# Voeding.net
KiCad netlist of a schematic drawn in Altium Designer
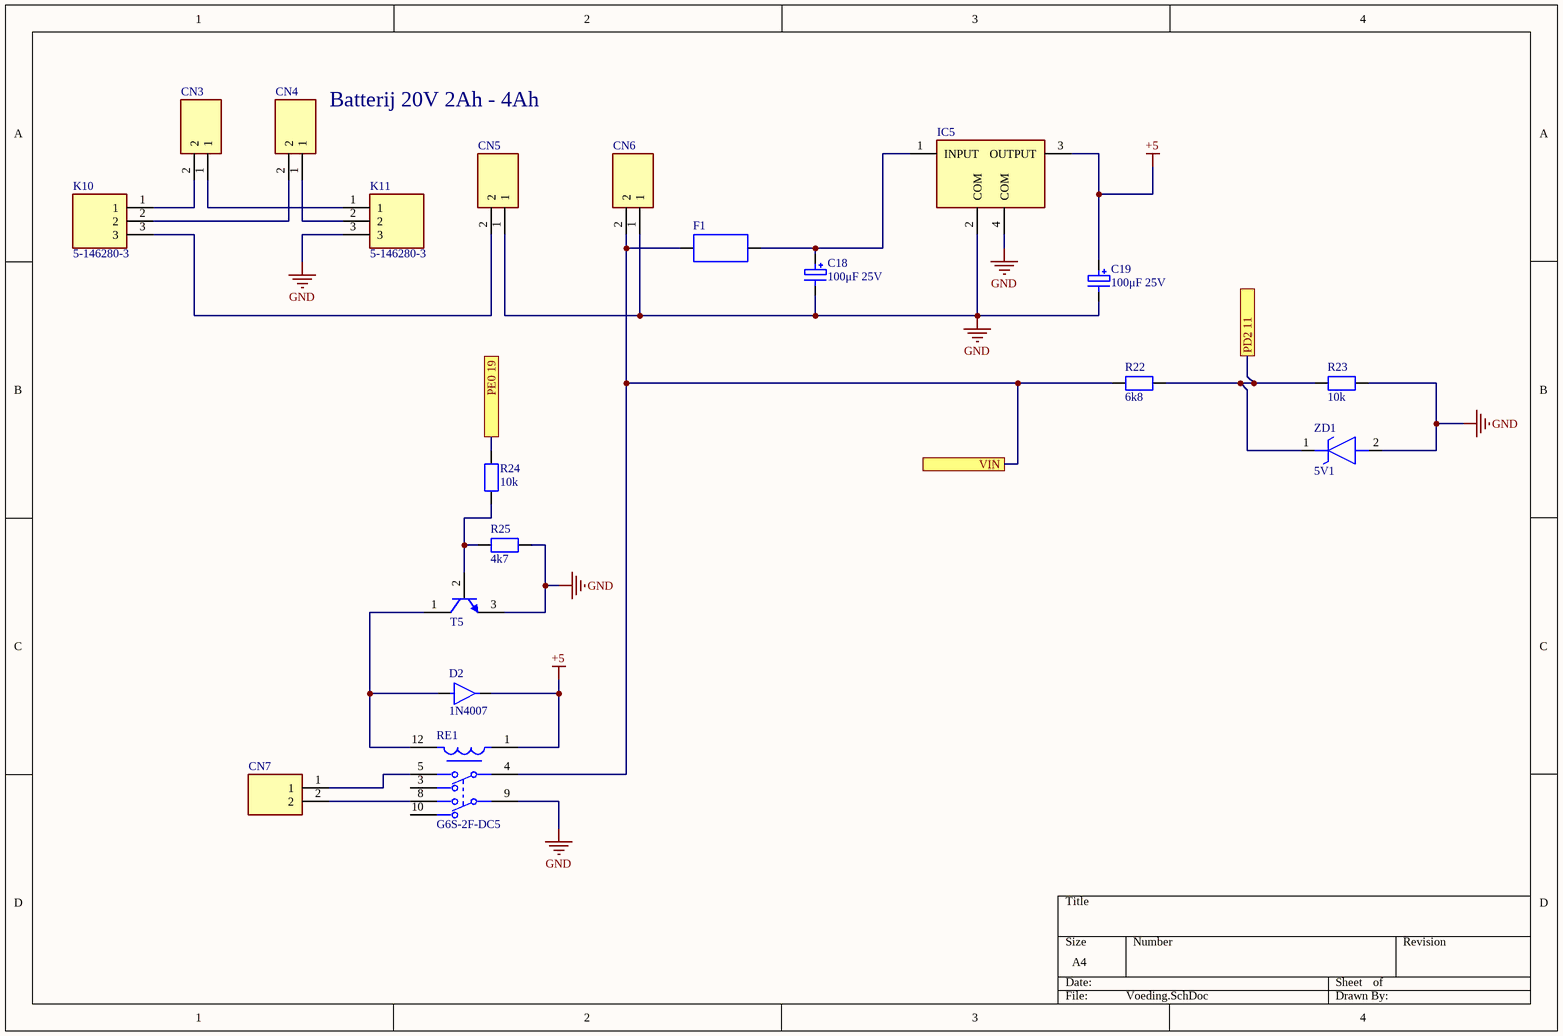
[diagram p0: Voeding.SchDoc]

(export (version "E")
  (design (tool "Eeschema 10.0.6"))
  (components
    (comp (ref "C18")
      (value "100μF 25V")
      (footprint "Elco 100uF 25V")
      (fields
        (field (name "PART NUMBER") "02015A270JAT2A")
        (field (name "MANUFACTURER") "AVX Interconnect / Elco")
      )
      (libsource (lib "Soldeerstation") (part "Condensator Elco"))
    )
    (comp (ref "C19")
      (value "100μF 25V")
      (footprint "Elco 100uF 25V")
      (fields
        (field (name "PART NUMBER") "02015A270JAT2A")
        (field (name "MANUFACTURER") "AVX Interconnect / Elco")
      )
      (libsource (lib "Soldeerstation") (part "Condensator Elco"))
    )
    (comp (ref "CN3")
      (value "282836-2")
      (footprint "Schroefconnector 2 Pin")
      (description "Connector")
      (libsource (lib "Soldeerstation") (part "Schroefconnector 2 Pin L"))
    )
    (comp (ref "CN4")
      (value "282836-2")
      (footprint "Schroefconnector 2 Pin")
      (description "Connector")
      (libsource (lib "Soldeerstation") (part "Schroefconnector 2 Pin L"))
    )
    (comp (ref "CN5")
      (value "282836-2")
      (footprint "Schroefconnector 2 Pin")
      (description "Connector")
      (libsource (lib "Soldeerstation") (part "Schroefconnector 2 Pin L"))
    )
    (comp (ref "CN6")
      (value "282836-2")
      (footprint "Schroefconnector 2 Pin")
      (description "Connector")
      (libsource (lib "Soldeerstation") (part "Schroefconnector 2 Pin L"))
    )
    (comp (ref "CN7")
      (value "282836-2")
      (footprint "Schroefconnector 2 Pin")
      (description "Connector")
      (libsource (lib "") (part "Schroefconnector 2 Pin L_1"))
    )
    (comp (ref "D2")
      (value "1N4007")
      (footprint "1N4007")
      (description "1000 V, 1 A")
      (fields (field (name "VOLTAGE") "100V"))
      (libsource (lib "Soldeerstation") (part "1N4007"))
    )
    (comp (ref "F1")
      (value "696101000002")
      (footprint "FuseHolder")
      (libsource (lib "Soldeerstation") (part "FuseHolder"))
    )
    (comp (ref "IC5")
      (value "TL780-05CKTTR")
      (footprint "DC-DC Convertor")
      (description "IC REG LIN 5V 1.5A DDPAK/TO263-3")
      (libsource (lib "Soldeerstation") (part "DC/DC Convertor"))
    )
    (comp (ref "K10")
      (value "5-146280-3")
      (footprint "3 Pin Header")
      (description "Connector 5-146280-3")
      (fields (field (name "MOUSER2 PART NUMBER") "571-5-146280-3"))
      (libsource (lib "") (part "3 Pin Header_1"))
    )
    (comp (ref "K11")
      (value "5-146280-3")
      (footprint "3 Pin Header")
      (description "Connector 5-146280-3")
      (fields (field (name "MOUSER2 PART NUMBER") "571-5-146280-3"))
      (libsource (lib "Soldeerstation") (part "3 Pin Header"))
    )
    (comp (ref "R22")
      (value "6k8")
      (footprint "Resistor")
      (description "Resistor")
      (fields (field (name "MANUFACTURER") "Vishay Dale") (field (name "PART NUMBER") "CRCW08050000Z0EA"))
      (libsource (lib "Soldeerstation") (part "Resistor"))
    )
    (comp (ref "R23")
      (value "10k")
      (footprint "Resistor")
      (description "Resistor")
      (fields (field (name "MANUFACTURER") "Vishay Dale") (field (name "PART NUMBER") "CRCW08050000Z0EA"))
      (libsource (lib "Soldeerstation") (part "Resistor"))
    )
    (comp (ref "R24")
      (value "10k")
      (footprint "Resistor")
      (description "Resistor")
      (fields (field (name "MANUFACTURER") "Vishay Dale") (field (name "PART NUMBER") "CRCW08050000Z0EA"))
      (libsource (lib "Soldeerstation") (part "Resistor"))
    )
    (comp (ref "R25")
      (value "4k7")
      (footprint "Resistor")
      (description "Resistor")
      (fields (field (name "MANUFACTURER") "Vishay Dale") (field (name "PART NUMBER") "CRCW08050000Z0EA"))
      (libsource (lib "Soldeerstation") (part "Resistor"))
    )
    (comp (ref "RE1")
      (value "G6S-2F-DC5")
      (footprint "Relay")
      (description "RELAY TELECOM DPDT 2A 5VDC")
      (fields
        (field (name "MANUFACTURER") "Omron")
        (field (name "OCTOPART") "https://octopart.com/g6s-2f-dc5-omron-85236")
      )
      (libsource (lib "Soldeerstation") (part "Relay"))
    )
    (comp (ref "T5")
      (value "BC547CZL1G")
      (footprint "BC547C")
      (description "BC547C, 45 V, 100 mA, 500 mW,\r\nhfe = 400")
      (fields (field (name "MANUFACTURER") "On Semiconductor"))
      (libsource (lib "Soldeerstation") (part "BC547C"))
    )
    (comp (ref "ZD1")
      (value "5V1")
      (footprint "ZenerDiode")
      (description "zenerdiode 5,1 V, 500 mW")
      (libsource (lib "Soldeerstation") (part "ZenerDiode"))
    )
  )
  (nets
    (net (code "1") (name "+5") (class "Default")
      (node (ref "C19") (pin "1") (pinfunction "1_1") (pintype "passive"))
      (node (ref "D2") (pin "1") (pinfunction "C_1") (pintype "passive"))
      (node (ref "IC5") (pin "3") (pinfunction "OUTPUT_3") (pintype "power_in"))
      (node (ref "RE1") (pin "1") (pinfunction "1_1") (pintype "passive"))
    )
    (net (code "2") (name "/PD2 11") (class "Default")
      (node (ref "R22") (pin "2") (pinfunction "2_2") (pintype "passive"))
      (node (ref "R23") (pin "1") (pintype "passive"))
      (node (ref "ZD1") (pin "1") (pinfunction "K_1") (pintype "passive"))
    )
    (net (code "3") (name "/PE0 19") (class "Default")
      (node (ref "R24") (pin "2") (pinfunction "2_2") (pintype "passive"))
    )
    (net (code "4") (name "/VIN") (class "Default")
      (node (ref "CN6") (pin "2") (pinfunction "2_2") (pintype "passive"))
      (node (ref "F1") (pin "1") (pinfunction "1_1") (pintype "passive"))
      (node (ref "R22") (pin "1") (pintype "passive"))
      (node (ref "RE1") (pin "4") (pinfunction "4_4") (pintype "passive"))
    )
    (net (code "5") (name "GND") (class "Default")
      (node (ref "C18") (pin "2") (pinfunction "2_2") (pintype "passive"))
      (node (ref "C19") (pin "2") (pinfunction "2_2") (pintype "passive"))
      (node (ref "CN5") (pin "1") (pinfunction "1_1") (pintype "passive"))
      (node (ref "CN6") (pin "1") (pinfunction "1_1") (pintype "passive"))
      (node (ref "IC5") (pin "2") (pinfunction "COM_2") (pintype "passive"))
      (node (ref "IC5") (pin "4") (pinfunction "COM_4") (pintype "passive"))
      (node (ref "K11") (pin "3") (pinfunction "3_3") (pintype "passive"))
      (node (ref "R23") (pin "2") (pinfunction "2_2") (pintype "passive"))
      (node (ref "R25") (pin "2") (pinfunction "2_2") (pintype "passive"))
      (node (ref "RE1") (pin "9") (pinfunction "9_9") (pintype "passive"))
      (node (ref "T5") (pin "3") (pinfunction "E_3") (pintype "passive"))
      (node (ref "ZD1") (pin "2") (pinfunction "A_2") (pintype "passive"))
    )
    (net (code "6") (name "Net-(CN3-Pad1)") (class "Default")
      (node (ref "CN3") (pin "1") (pinfunction "1_1") (pintype "passive"))
      (node (ref "K11") (pin "1") (pinfunction "1_1") (pintype "passive"))
    )
    (net (code "7") (name "Net-(CN3-Pad2)") (class "Default")
      (node (ref "CN3") (pin "2") (pinfunction "2_2") (pintype "passive"))
      (node (ref "K10") (pin "1") (pinfunction "1_1") (pintype "passive"))
    )
    (net (code "8") (name "Net-(CN4-Pad1)") (class "Default")
      (node (ref "CN4") (pin "1") (pinfunction "1_1") (pintype "passive"))
      (node (ref "K11") (pin "2") (pinfunction "2_2") (pintype "passive"))
    )
    (net (code "9") (name "Net-(CN4-Pad2)") (class "Default")
      (node (ref "CN4") (pin "2") (pinfunction "2_2") (pintype "passive"))
      (node (ref "K10") (pin "2") (pinfunction "2_2") (pintype "passive"))
    )
    (net (code "10") (name "Net-(CN5-Pad2)") (class "Default")
      (node (ref "CN5") (pin "2") (pinfunction "2_2") (pintype "passive"))
      (node (ref "K10") (pin "3") (pinfunction "3_3") (pintype "passive"))
    )
    (net (code "11") (name "Net-(CN7-Pad1)") (class "Default")
      (node (ref "CN7") (pin "1") (pinfunction "1_1") (pintype "passive"))
      (node (ref "RE1") (pin "5") (pinfunction "5_5") (pintype "passive"))
    )
    (net (code "12") (name "Net-(CN7-Pad2)") (class "Default")
      (node (ref "CN7") (pin "2") (pinfunction "2_2") (pintype "passive"))
      (node (ref "RE1") (pin "8") (pinfunction "8_8") (pintype "passive"))
    )
    (net (code "13") (name "Net-(D2-A)") (class "Default")
      (node (ref "D2") (pin "2") (pinfunction "A_2") (pintype "passive"))
      (node (ref "RE1") (pin "12") (pinfunction "12_12") (pintype "passive"))
      (node (ref "T5") (pin "1") (pinfunction "C_1") (pintype "passive"))
    )
    (net (code "14") (name "Net-(IC5-INPUT)") (class "Default")
      (node (ref "C18") (pin "1") (pinfunction "1_1") (pintype "passive"))
      (node (ref "F1") (pin "2") (pinfunction "2_2") (pintype "passive"))
      (node (ref "IC5") (pin "1") (pinfunction "INPUT_1") (pintype "power_in"))
    )
    (net (code "15") (name "Net-(T5-B)") (class "Default")
      (node (ref "R24") (pin "1") (pintype "passive"))
      (node (ref "R25") (pin "1") (pintype "passive"))
      (node (ref "T5") (pin "2") (pinfunction "B_2") (pintype "passive"))
    )
    (net (code "16") (name "unconnected-(RE1-Pad3)") (class "Default")
      (node (ref "RE1") (pin "3") (pinfunction "3_3") (pintype "passive"))
    )
    (net (code "17") (name "unconnected-(RE1-Pad10)") (class "Default")
      (node (ref "RE1") (pin "10") (pinfunction "10_10") (pintype "passive"))
    )
  )
)
